# realtalker.net
KiCad netlist of a schematic drawn in EAGLE
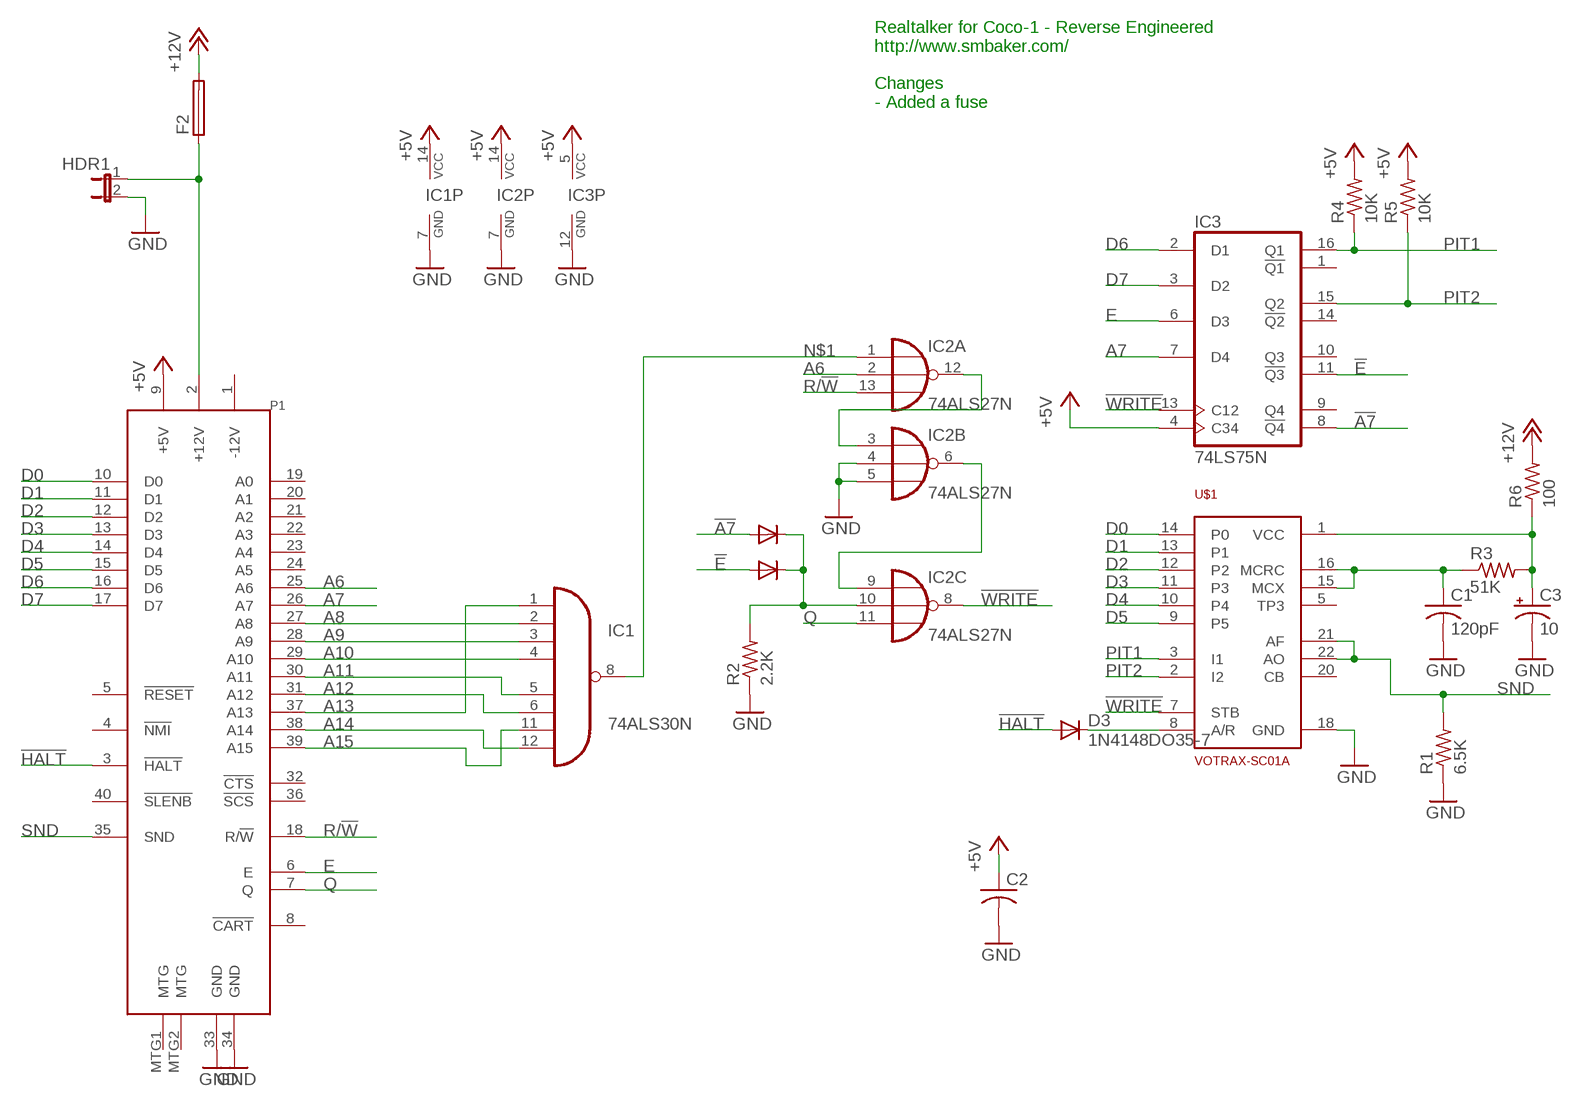
[diagram p0: schematic, sheet 1]

(export (version "E")
  (design (tool "Eeschema 10.0.6"))
  (components
    (comp (ref "C1")
      (value "120pF")
      (footprint "eagle-import:C025-025X050")
      (libsource (lib "eagle-import") (part "C-US025-025X050"))
    )
    (comp (ref "C2")
      (value "C-US025-025X050")
      (footprint "eagle-import:C025-025X050")
      (libsource (lib "eagle-import") (part "C-US025-025X050"))
    )
    (comp (ref "C3")
      (value "10")
      (footprint "eagle-import:E2,5-6")
      (libsource (lib "eagle-import") (part "CPOL-USE2.5-6"))
    )
    (comp (ref "D1")
      (value "1N4148DO35-7")
      (footprint "eagle-import:DO35-7")
      (libsource (lib "eagle-import") (part "1N4148DO35-7"))
    )
    (comp (ref "D2")
      (value "1N4148DO35-7")
      (footprint "eagle-import:DO35-7")
      (libsource (lib "eagle-import") (part "1N4148DO35-7"))
    )
    (comp (ref "D3")
      (value "1N4148DO35-7")
      (footprint "eagle-import:DO35-7")
      (libsource (lib "eagle-import") (part "1N4148DO35-7"))
    )
    (comp (ref "F2")
      (value "PTC_FUSE")
      (footprint "eagle-import:PTC_0.400")
      (libsource (lib "eagle-import") (part "PTC_FUSE"))
    )
    (comp (ref "HDR1")
      (value "JP1E")
      (footprint "eagle-import:JP1")
      (libsource (lib "eagle-import") (part "JP1E"))
    )
    (comp (ref "IC1")
      (value "74ALS30N")
      (footprint "eagle-import:DIL14")
      (libsource (lib "eagle-import") (part "7430NALS"))
    )
    (comp (ref "IC2")
      (value "74ALS27N")
      (footprint "eagle-import:DIL14")
      (libsource (lib "eagle-import") (part "7427NALS"))
    )
    (comp (ref "IC3")
      (value "74LS75N")
      (footprint "eagle-import:DIL16")
      (libsource (lib "eagle-import") (part "7475NLS"))
    )
    (comp (ref "P1")
      (value "COCO-CARTRT")
      (footprint "eagle-import:COCO-CART-RT")
      (libsource (lib "eagle-import") (part "COCO-CARTRT"))
    )
    (comp (ref "R1")
      (value "6.5K")
      (footprint "eagle-import:0204_7")
      (libsource (lib "eagle-import") (part "R-US_0204/7"))
    )
    (comp (ref "R2")
      (value "2.2K")
      (footprint "eagle-import:0204_7")
      (libsource (lib "eagle-import") (part "R-US_0204/7"))
    )
    (comp (ref "R3")
      (value "51K")
      (footprint "eagle-import:0204_7")
      (libsource (lib "eagle-import") (part "R-US_0204/7"))
    )
    (comp (ref "R4")
      (value "10K")
      (footprint "eagle-import:0204_7")
      (libsource (lib "eagle-import") (part "R-US_0204/7"))
    )
    (comp (ref "R5")
      (value "10K")
      (footprint "eagle-import:0204_7")
      (libsource (lib "eagle-import") (part "R-US_0204/7"))
    )
    (comp (ref "R6")
      (value "100")
      (footprint "eagle-import:0204_7")
      (libsource (lib "eagle-import") (part "R-US_0204/7"))
    )
    (comp (ref "U$1")
      (value "VOTRAX-SC01A")
      (footprint "eagle-import:DIL22-4")
      (libsource (lib "eagle-import") (part "VOTRAX-SC01A"))
    )
  )
  (nets
    (net (code "1") (name "+5V") (class "Default")
      (node (ref "C2") (pin "1") (pinfunction "1_1") (pintype "passive"))
      (node (ref "IC1") (pin "14") (pinfunction "VCC_14") (pintype "power_in"))
      (node (ref "IC2") (pin "14") (pinfunction "VCC_14") (pintype "power_in"))
      (node (ref "IC3") (pin "4") (pinfunction "C34_4") (pintype "input"))
      (node (ref "IC3") (pin "5") (pinfunction "VCC_5") (pintype "power_in"))
      (node (ref "P1") (pin "9") (pinfunction "+5V_9") (pintype "passive"))
      (node (ref "R4") (pin "2") (pinfunction "2_2") (pintype "passive"))
      (node (ref "R5") (pin "2") (pinfunction "2_2") (pintype "passive"))
    )
    (net (code "2") (name "+12V") (class "Default")
      (node (ref "F2") (pin "2") (pinfunction "2_2") (pintype "passive"))
      (node (ref "R6") (pin "2") (pinfunction "2_2") (pintype "passive"))
    )
    (net (code "3") (name "/A6") (class "Default")
      (node (ref "IC2") (pin "2") (pinfunction "I1_2") (pintype "input"))
      (node (ref "P1") (pin "25") (pinfunction "A6_25") (pintype "output"))
    )
    (net (code "4") (name "/A7") (class "Default")
      (node (ref "IC3") (pin "7") (pinfunction "D4_7") (pintype "input"))
      (node (ref "P1") (pin "26") (pinfunction "A7_26") (pintype "output"))
    )
    (net (code "5") (name "/A8") (class "Default")
      (node (ref "IC1") (pin "2") (pinfunction "I1_2") (pintype "input"))
      (node (ref "P1") (pin "27") (pinfunction "A8_27") (pintype "output"))
    )
    (net (code "6") (name "/A9") (class "Default")
      (node (ref "IC1") (pin "3") (pinfunction "I2_3") (pintype "input"))
      (node (ref "P1") (pin "28") (pinfunction "A9_28") (pintype "output"))
    )
    (net (code "7") (name "/A10") (class "Default")
      (node (ref "IC1") (pin "4") (pinfunction "I3_4") (pintype "input"))
      (node (ref "P1") (pin "29") (pinfunction "A10_29") (pintype "output"))
    )
    (net (code "8") (name "/A11") (class "Default")
      (node (ref "IC1") (pin "5") (pinfunction "I4_5") (pintype "input"))
      (node (ref "P1") (pin "30") (pinfunction "A11_30") (pintype "output"))
    )
    (net (code "9") (name "/A12") (class "Default")
      (node (ref "IC1") (pin "6") (pinfunction "I5_6") (pintype "input"))
      (node (ref "P1") (pin "31") (pinfunction "A12_31") (pintype "output"))
    )
    (net (code "10") (name "/A13") (class "Default")
      (node (ref "IC1") (pin "1") (pinfunction "I0_1") (pintype "input"))
      (node (ref "P1") (pin "37") (pinfunction "A13_37") (pintype "output"))
    )
    (net (code "11") (name "/A14") (class "Default")
      (node (ref "IC1") (pin "12") (pinfunction "I7_12") (pintype "input"))
      (node (ref "P1") (pin "38") (pinfunction "A14_38") (pintype "output"))
    )
    (net (code "12") (name "/A15") (class "Default")
      (node (ref "IC1") (pin "11") (pinfunction "I6_11") (pintype "input"))
      (node (ref "P1") (pin "39") (pinfunction "A15_39") (pintype "output"))
    )
    (net (code "13") (name "/D0") (class "Default")
      (node (ref "P1") (pin "10") (pinfunction "D0_10") (pintype "bidirectional"))
      (node (ref "U$1") (pin "14") (pinfunction "P0_14") (pintype "bidirectional"))
    )
    (net (code "14") (name "/D1") (class "Default")
      (node (ref "P1") (pin "11") (pinfunction "D1_11") (pintype "bidirectional"))
      (node (ref "U$1") (pin "13") (pinfunction "P1_13") (pintype "bidirectional"))
    )
    (net (code "15") (name "/D2") (class "Default")
      (node (ref "P1") (pin "12") (pinfunction "D2_12") (pintype "bidirectional"))
      (node (ref "U$1") (pin "12") (pinfunction "P2_12") (pintype "bidirectional"))
    )
    (net (code "16") (name "/D3") (class "Default")
      (node (ref "P1") (pin "13") (pinfunction "D3_13") (pintype "bidirectional"))
      (node (ref "U$1") (pin "11") (pinfunction "P3_11") (pintype "bidirectional"))
    )
    (net (code "17") (name "/D4") (class "Default")
      (node (ref "P1") (pin "14") (pinfunction "D4_14") (pintype "bidirectional"))
      (node (ref "U$1") (pin "10") (pinfunction "P4_10") (pintype "bidirectional"))
    )
    (net (code "18") (name "/D5") (class "Default")
      (node (ref "P1") (pin "15") (pinfunction "D5_15") (pintype "bidirectional"))
      (node (ref "U$1") (pin "9") (pinfunction "P5_9") (pintype "bidirectional"))
    )
    (net (code "19") (name "/D6") (class "Default")
      (node (ref "IC3") (pin "2") (pinfunction "D1_2") (pintype "input"))
      (node (ref "P1") (pin "16") (pinfunction "D6_16") (pintype "bidirectional"))
    )
    (net (code "20") (name "/D7") (class "Default")
      (node (ref "IC3") (pin "3") (pinfunction "D2_3") (pintype "input"))
      (node (ref "P1") (pin "17") (pinfunction "D7_17") (pintype "bidirectional"))
    )
    (net (code "21") (name "/E") (class "Default")
      (node (ref "IC3") (pin "6") (pinfunction "D3_6") (pintype "input"))
      (node (ref "P1") (pin "6") (pinfunction "E_6") (pintype "output"))
    )
    (net (code "22") (name "/N$1") (class "Default")
      (node (ref "IC1") (pin "8") (pinfunction "O_8") (pintype "output"))
      (node (ref "IC2") (pin "1") (pinfunction "I0_1") (pintype "input"))
    )
    (net (code "23") (name "/PIT1") (class "Default")
      (node (ref "IC3") (pin "16") (pinfunction "Q1_16") (pintype "output"))
      (node (ref "R4") (pin "1") (pinfunction "1_1") (pintype "passive"))
      (node (ref "U$1") (pin "3") (pinfunction "I1_3") (pintype "bidirectional"))
    )
    (net (code "24") (name "/PIT2") (class "Default")
      (node (ref "IC3") (pin "15") (pinfunction "Q2_15") (pintype "output"))
      (node (ref "R5") (pin "1") (pinfunction "1_1") (pintype "passive"))
      (node (ref "U$1") (pin "2") (pinfunction "I2_2") (pintype "bidirectional"))
    )
    (net (code "25") (name "/Q") (class "Default")
      (node (ref "IC2") (pin "11") (pinfunction "I2_11") (pintype "input"))
      (node (ref "P1") (pin "7") (pinfunction "Q_7") (pintype "output"))
    )
    (net (code "26") (name "/R{slash}~{W}") (class "Default")
      (node (ref "IC2") (pin "13") (pinfunction "I2_13") (pintype "input"))
      (node (ref "P1") (pin "18") (pinfunction "R/~{W}_18") (pintype "output"))
    )
    (net (code "27") (name "/SND") (class "Default")
      (node (ref "P1") (pin "35") (pinfunction "SND_35") (pintype "bidirectional"))
      (node (ref "R1") (pin "2") (pinfunction "2_2") (pintype "passive"))
      (node (ref "U$1") (pin "21") (pinfunction "AF_21") (pintype "bidirectional"))
      (node (ref "U$1") (pin "22") (pinfunction "AO_22") (pintype "bidirectional"))
    )
    (net (code "28") (name "/~{A7}") (class "Default")
      (node (ref "D2") (pin "A") (pinfunction "A_A") (pintype "passive"))
      (node (ref "IC3") (pin "8") (pinfunction "~{Q4}_8") (pintype "output"))
    )
    (net (code "29") (name "/~{E}") (class "Default")
      (node (ref "D1") (pin "A") (pinfunction "A_A") (pintype "passive"))
      (node (ref "IC3") (pin "11") (pinfunction "~{Q3}_11") (pintype "output"))
    )
    (net (code "30") (name "/~{HALT}") (class "Default")
      (node (ref "D3") (pin "A") (pinfunction "A_A") (pintype "passive"))
      (node (ref "P1") (pin "3") (pinfunction "~{HALT}_3") (pintype "bidirectional"))
    )
    (net (code "31") (name "/~{WRITE}") (class "Default")
      (node (ref "IC2") (pin "8") (pinfunction "O_8") (pintype "output"))
      (node (ref "IC3") (pin "13") (pinfunction "C12_13") (pintype "input"))
      (node (ref "U$1") (pin "7") (pinfunction "STB_7") (pintype "bidirectional"))
    )
    (net (code "32") (name "GND") (class "Default")
      (node (ref "C1") (pin "2") (pinfunction "2_2") (pintype "passive"))
      (node (ref "C2") (pin "2") (pinfunction "2_2") (pintype "passive"))
      (node (ref "C3") (pin "-") (pinfunction "-_-") (pintype "passive"))
      (node (ref "HDR1") (pin "2") (pinfunction "2_2") (pintype "passive"))
      (node (ref "IC1") (pin "7") (pinfunction "GND_7") (pintype "power_in"))
      (node (ref "IC2") (pin "4") (pinfunction "I1_4") (pintype "input"))
      (node (ref "IC2") (pin "5") (pinfunction "I2_5") (pintype "input"))
      (node (ref "IC2") (pin "7") (pinfunction "GND_7") (pintype "power_in"))
      (node (ref "IC3") (pin "12") (pinfunction "GND_12") (pintype "power_in"))
      (node (ref "P1") (pin "33") (pinfunction "GND_33") (pintype "passive"))
      (node (ref "P1") (pin "34") (pinfunction "GND_34") (pintype "passive"))
      (node (ref "R1") (pin "1") (pinfunction "1_1") (pintype "passive"))
      (node (ref "R2") (pin "1") (pinfunction "1_1") (pintype "passive"))
      (node (ref "U$1") (pin "18") (pinfunction "GND_18") (pintype "bidirectional"))
    )
    (net (code "33") (name "Net-(IC2A-O)") (class "Default")
      (node (ref "IC2") (pin "12") (pinfunction "O_12") (pintype "output"))
      (node (ref "IC2") (pin "3") (pinfunction "I0_3") (pintype "input"))
    )
    (net (code "34") (name "Net-(IC2B-O)") (class "Default")
      (node (ref "IC2") (pin "6") (pinfunction "O_6") (pintype "output"))
      (node (ref "IC2") (pin "9") (pinfunction "I0_9") (pintype "input"))
    )
    (net (code "35") (name "Net-(IC2C-I1)") (class "Default")
      (node (ref "D1") (pin "C") (pinfunction "C_C") (pintype "passive"))
      (node (ref "D2") (pin "C") (pinfunction "C_C") (pintype "passive"))
      (node (ref "IC2") (pin "10") (pinfunction "I1_10") (pintype "input"))
      (node (ref "R2") (pin "2") (pinfunction "2_2") (pintype "passive"))
    )
    (net (code "36") (name "Net-(P1-+12V)") (class "Default")
      (node (ref "F2") (pin "1") (pinfunction "1_1") (pintype "passive"))
      (node (ref "HDR1") (pin "1") (pinfunction "1_1") (pintype "passive"))
      (node (ref "P1") (pin "2") (pinfunction "+12V_2") (pintype "passive"))
    )
    (net (code "37") (name "Net-(U$1-A{slash}R)") (class "Default")
      (node (ref "D3") (pin "C") (pinfunction "C_C") (pintype "passive"))
      (node (ref "U$1") (pin "8") (pinfunction "A/R_8") (pintype "bidirectional"))
    )
    (net (code "38") (name "Net-(U$1-MCRC)") (class "Default")
      (node (ref "C1") (pin "1") (pinfunction "1_1") (pintype "passive"))
      (node (ref "R3") (pin "1") (pinfunction "1_1") (pintype "passive"))
      (node (ref "U$1") (pin "15") (pinfunction "MCX_15") (pintype "bidirectional"))
      (node (ref "U$1") (pin "16") (pinfunction "MCRC_16") (pintype "bidirectional"))
    )
    (net (code "39") (name "Net-(U$1-VCC)") (class "Default")
      (node (ref "C3") (pin "+") (pinfunction "+_+") (pintype "passive"))
      (node (ref "R3") (pin "2") (pinfunction "2_2") (pintype "passive"))
      (node (ref "R6") (pin "1") (pinfunction "1_1") (pintype "passive"))
      (node (ref "U$1") (pin "1") (pinfunction "VCC_1") (pintype "bidirectional"))
    )
    (net (code "40") (name "unconnected-(IC3A-Q3-Pad10)") (class "Default")
      (node (ref "IC3") (pin "10") (pinfunction "Q3_10") (pintype "output"))
    )
    (net (code "41") (name "unconnected-(IC3A-Q4-Pad9)") (class "Default")
      (node (ref "IC3") (pin "9") (pinfunction "Q4_9") (pintype "output"))
    )
    (net (code "42") (name "unconnected-(IC3A-~{Q1}-Pad1)") (class "Default")
      (node (ref "IC3") (pin "1") (pinfunction "~{Q1}_1") (pintype "output"))
    )
    (net (code "43") (name "unconnected-(IC3A-~{Q2}-Pad14)") (class "Default")
      (node (ref "IC3") (pin "14") (pinfunction "~{Q2}_14") (pintype "output"))
    )
    (net (code "44") (name "unconnected-(P1--12V-Pad1)") (class "Default")
      (node (ref "P1") (pin "1") (pinfunction "-12V_1") (pintype "passive"))
    )
    (net (code "45") (name "unconnected-(P1-A0-Pad19)") (class "Default")
      (node (ref "P1") (pin "19") (pinfunction "A0_19") (pintype "output"))
    )
    (net (code "46") (name "unconnected-(P1-A1-Pad20)") (class "Default")
      (node (ref "P1") (pin "20") (pinfunction "A1_20") (pintype "output"))
    )
    (net (code "47") (name "unconnected-(P1-A2-Pad21)") (class "Default")
      (node (ref "P1") (pin "21") (pinfunction "A2_21") (pintype "output"))
    )
    (net (code "48") (name "unconnected-(P1-A3-Pad22)") (class "Default")
      (node (ref "P1") (pin "22") (pinfunction "A3_22") (pintype "output"))
    )
    (net (code "49") (name "unconnected-(P1-A4-Pad23)") (class "Default")
      (node (ref "P1") (pin "23") (pinfunction "A4_23") (pintype "output"))
    )
    (net (code "50") (name "unconnected-(P1-A5-Pad24)") (class "Default")
      (node (ref "P1") (pin "24") (pinfunction "A5_24") (pintype "output"))
    )
    (net (code "51") (name "unconnected-(P1-MTG-PadMTG1)") (class "Default")
      (node (ref "P1") (pin "MTG1") (pinfunction "MTG_MTG1") (pintype "passive"))
    )
    (net (code "52") (name "unconnected-(P1-MTG-PadMTG2)") (class "Default")
      (node (ref "P1") (pin "MTG2") (pinfunction "MTG_MTG2") (pintype "passive"))
    )
    (net (code "53") (name "unconnected-(P1-~{CART}-Pad8)") (class "Default")
      (node (ref "P1") (pin "8") (pinfunction "~{CART}_8") (pintype "input"))
    )
    (net (code "54") (name "unconnected-(P1-~{CTS}-Pad32)") (class "Default")
      (node (ref "P1") (pin "32") (pinfunction "~{CTS}_32") (pintype "output"))
    )
    (net (code "55") (name "unconnected-(P1-~{NMI}-Pad4)") (class "Default")
      (node (ref "P1") (pin "4") (pinfunction "~{NMI}_4") (pintype "bidirectional"))
    )
    (net (code "56") (name "unconnected-(P1-~{RESET}-Pad5)") (class "Default")
      (node (ref "P1") (pin "5") (pinfunction "~{RESET}_5") (pintype "bidirectional"))
    )
    (net (code "57") (name "unconnected-(P1-~{SCS}-Pad36)") (class "Default")
      (node (ref "P1") (pin "36") (pinfunction "~{SCS}_36") (pintype "output"))
    )
    (net (code "58") (name "unconnected-(P1-~{SLENB}-Pad40)") (class "Default")
      (node (ref "P1") (pin "40") (pinfunction "~{SLENB}_40") (pintype "input"))
    )
    (net (code "59") (name "unconnected-(U$1-CB-Pad20)") (class "Default")
      (node (ref "U$1") (pin "20") (pinfunction "CB_20") (pintype "bidirectional"))
    )
    (net (code "60") (name "unconnected-(U$1-TP3-Pad5)") (class "Default")
      (node (ref "U$1") (pin "5") (pinfunction "TP3_5") (pintype "bidirectional"))
    )
  )
)
